# wireframe_sch.net
KiCad netlist of a schematic drawn in Altium Designer
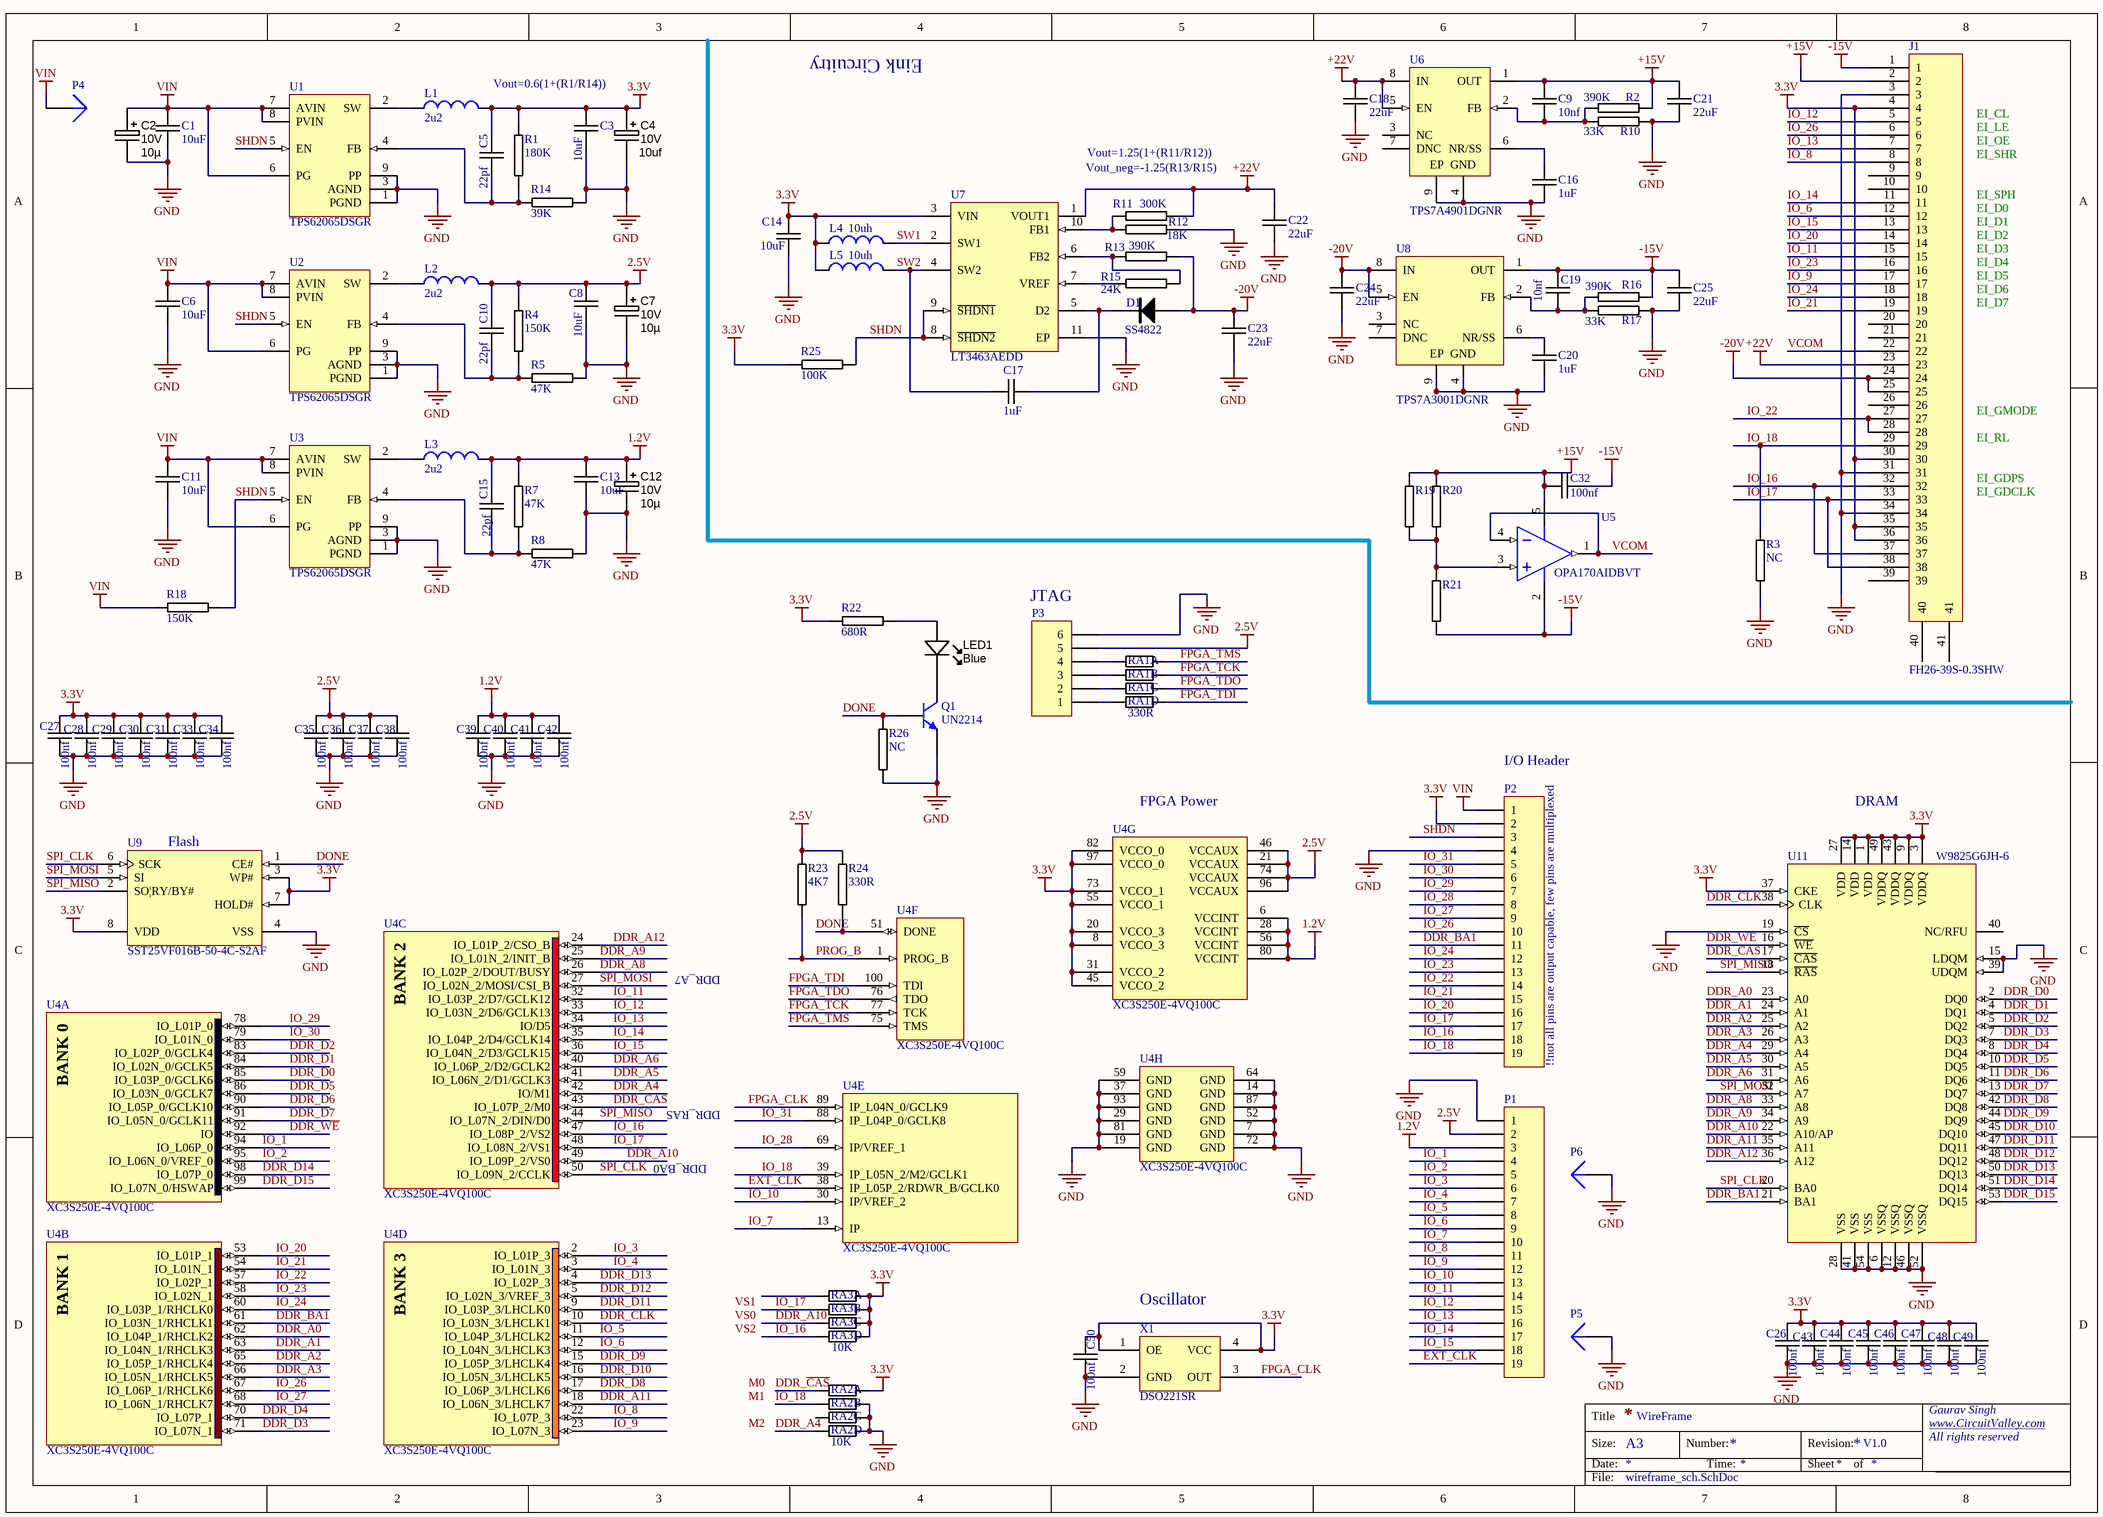
[diagram p0: wireframe_sch.SchDoc]

(export (version "E")
  (design (tool "Eeschema 10.0.6"))
  (components
    (comp (ref "C1")
      (value "10uF")
      (footprint "0603C-GENERIC")
      (description "CAPACITOR 0603 CERAMIC")
      (fields
        (field (name "MANUFACTURER") "Murata Electronics North America")
        (field (name "MANUFACTURER PART NUMBER") "GRM188R60J106ME47D")
      )
      (libsource (lib "Generic") (part "0603C-10UF-6V3-X5R-MUR"))
    )
    (comp (ref "C2")
      (value "10µ")
      (footprint "CAPMP3528X210N")
      (description "Capacitor SMD Tantalum 47uF 20% 6.3V 1210")
      (fields (field (name "TOLERANCE") "±20%") (field (name "RATINGS") "10V"))
      (libsource (lib "PBL - Capacitors") (part "CAPT_47u_1210_6V3"))
    )
    (comp (ref "C3")
      (value "10uF")
      (footprint "0603C-GENERIC")
      (description "CAPACITOR 0603 CERAMIC")
      (fields
        (field (name "MANUFACTURER") "Murata Electronics North America")
        (field (name "MANUFACTURER PART NUMBER") "GRM188R60J106ME47D")
      )
      (libsource (lib "Generic") (part "0603C-10UF-6V3-X5R-MUR"))
    )
    (comp (ref "C4")
      (value "10uf")
      (footprint "CAPMP3528X210N")
      (description "Capacitor SMD Tantalum 47uF 20% 6.3V 1210")
      (fields (field (name "TOLERANCE") "±20%") (field (name "RATINGS") "10V"))
      (libsource (lib "PBL - Capacitors") (part "CAPT_47u_1210_6V3"))
    )
    (comp (ref "C5")
      (value "22pf")
      (footprint "0603C-GENERIC")
      (description "CAPACITOR 0603 CERAMIC")
      (fields
        (field (name "MANUFACTURER") "Murata Electronics North America")
        (field (name "MANUFACTURER PART NUMBER") "GRM188R60J106ME47D")
      )
      (libsource (lib "Generic") (part "0603C-10UF-6V3-X5R-MUR"))
    )
    (comp (ref "C6")
      (value "10uF")
      (footprint "0603C-GENERIC")
      (description "CAPACITOR 0603 CERAMIC")
      (fields
        (field (name "MANUFACTURER") "Murata Electronics North America")
        (field (name "MANUFACTURER PART NUMBER") "GRM188R60J106ME47D")
      )
      (libsource (lib "Generic") (part "0603C-10UF-6V3-X5R-MUR"))
    )
    (comp (ref "C7")
      (value "10µ")
      (footprint "CAPMP3528X210N")
      (description "Capacitor SMD Tantalum 47uF 20% 6.3V 1210")
      (fields (field (name "TOLERANCE") "±20%") (field (name "RATINGS") "10V"))
      (libsource (lib "PBL - Capacitors") (part "CAPT_47u_1210_6V3"))
    )
    (comp (ref "C8")
      (value "10uF")
      (footprint "0603C-GENERIC")
      (description "CAPACITOR 0603 CERAMIC")
      (fields
        (field (name "MANUFACTURER") "Murata Electronics North America")
        (field (name "MANUFACTURER PART NUMBER") "GRM188R60J106ME47D")
      )
      (libsource (lib "Generic") (part "0603C-10UF-6V3-X5R-MUR"))
    )
    (comp (ref "C9")
      (value "10nf")
      (footprint "0603C-GENERIC")
      (description "CAPACITOR 0603 CERAMIC")
      (fields
        (field (name "MANUFACTURER") "Murata Electronics North America")
        (field (name "MANUFACTURER PART NUMBER") "GRM188R60J106ME47D")
      )
      (libsource (lib "Generic") (part "0603C-10UF-6V3-X5R-MUR"))
    )
    (comp (ref "C10")
      (value "22pf")
      (footprint "0603C-GENERIC")
      (description "CAPACITOR 0603 CERAMIC")
      (fields
        (field (name "MANUFACTURER") "Murata Electronics North America")
        (field (name "MANUFACTURER PART NUMBER") "GRM188R60J106ME47D")
      )
      (libsource (lib "Generic") (part "0603C-10UF-6V3-X5R-MUR"))
    )
    (comp (ref "C11")
      (value "10uF")
      (footprint "0603C-GENERIC")
      (description "CAPACITOR 0603 CERAMIC")
      (fields
        (field (name "MANUFACTURER") "Murata Electronics North America")
        (field (name "MANUFACTURER PART NUMBER") "GRM188R60J106ME47D")
      )
      (libsource (lib "Generic") (part "0603C-10UF-6V3-X5R-MUR"))
    )
    (comp (ref "C12")
      (value "10µ")
      (footprint "CAPMP3528X210N")
      (description "Capacitor SMD Tantalum 47uF 20% 6.3V 1210")
      (fields (field (name "TOLERANCE") "±20%") (field (name "RATINGS") "10V"))
      (libsource (lib "PBL - Capacitors") (part "CAPT_47u_1210_6V3"))
    )
    (comp (ref "C13")
      (value "10uF")
      (footprint "0603C-GENERIC")
      (description "CAPACITOR 0603 CERAMIC")
      (fields
        (field (name "MANUFACTURER") "Murata Electronics North America")
        (field (name "MANUFACTURER PART NUMBER") "GRM188R60J106ME47D")
      )
      (libsource (lib "Generic") (part "0603C-10UF-6V3-X5R-MUR"))
    )
    (comp (ref "C14")
      (value "10uF")
      (footprint "0603C-GENERIC")
      (description "CAPACITOR 0603 CERAMIC")
      (fields
        (field (name "MANUFACTURER") "Murata Electronics North America")
        (field (name "MANUFACTURER PART NUMBER") "GRM188R60J106ME47D")
      )
      (libsource (lib "Generic") (part "0603C-10UF-6V3-X5R-MUR"))
    )
    (comp (ref "C15")
      (value "22pf")
      (footprint "0603C-GENERIC")
      (description "CAPACITOR 0603 CERAMIC")
      (fields
        (field (name "MANUFACTURER") "Murata Electronics North America")
        (field (name "MANUFACTURER PART NUMBER") "GRM188R60J106ME47D")
      )
      (libsource (lib "Generic") (part "0603C-10UF-6V3-X5R-MUR"))
    )
    (comp (ref "C16")
      (value "1uF")
      (footprint "0603C-GENERIC")
      (description "CAPACITOR 0603 CERAMIC")
      (fields
        (field (name "MANUFACTURER") "Murata Electronics North America")
        (field (name "MANUFACTURER PART NUMBER") "GRM188R60J106ME47D")
      )
      (libsource (lib "Generic") (part "0603C-10UF-6V3-X5R-MUR"))
    )
    (comp (ref "C17")
      (value "1uF")
      (footprint "0603C-GENERIC")
      (description "CAPACITOR 0603 CERAMIC")
      (fields
        (field (name "MANUFACTURER") "Murata Electronics North America")
        (field (name "MANUFACTURER PART NUMBER") "GRM188R60J106ME47D")
      )
      (libsource (lib "Generic") (part "0603C-10UF-6V3-X5R-MUR"))
    )
    (comp (ref "C18")
      (value "22uF")
      (footprint "0603C-GENERIC")
      (description "CAPACITOR 0603 CERAMIC")
      (fields
        (field (name "MANUFACTURER") "Murata Electronics North America")
        (field (name "MANUFACTURER PART NUMBER") "GRM188R60J106ME47D")
      )
      (libsource (lib "Generic") (part "0603C-10UF-6V3-X5R-MUR"))
    )
    (comp (ref "C19")
      (value "10nf")
      (footprint "0603C-GENERIC")
      (description "CAPACITOR 0603 CERAMIC")
      (fields
        (field (name "MANUFACTURER") "Murata Electronics North America")
        (field (name "MANUFACTURER PART NUMBER") "GRM188R60J106ME47D")
      )
      (libsource (lib "Generic") (part "0603C-10UF-6V3-X5R-MUR"))
    )
    (comp (ref "C20")
      (value "1uF")
      (footprint "0603C-GENERIC")
      (description "CAPACITOR 0603 CERAMIC")
      (fields
        (field (name "MANUFACTURER") "Murata Electronics North America")
        (field (name "MANUFACTURER PART NUMBER") "GRM188R60J106ME47D")
      )
      (libsource (lib "Generic") (part "0603C-10UF-6V3-X5R-MUR"))
    )
    (comp (ref "C21")
      (value "22uF")
      (footprint "0603C-GENERIC")
      (description "CAPACITOR 0603 CERAMIC")
      (fields
        (field (name "MANUFACTURER") "Murata Electronics North America")
        (field (name "MANUFACTURER PART NUMBER") "GRM188R60J106ME47D")
      )
      (libsource (lib "Generic") (part "0603C-10UF-6V3-X5R-MUR"))
    )
    (comp (ref "C22")
      (value "22uF")
      (footprint "0603C-GENERIC")
      (description "CAPACITOR 0603 CERAMIC")
      (fields
        (field (name "MANUFACTURER") "Murata Electronics North America")
        (field (name "MANUFACTURER PART NUMBER") "GRM188R60J106ME47D")
      )
      (libsource (lib "Generic") (part "0603C-10UF-6V3-X5R-MUR"))
    )
    (comp (ref "C23")
      (value "22uF")
      (footprint "0603C-GENERIC")
      (description "CAPACITOR 0603 CERAMIC")
      (fields
        (field (name "MANUFACTURER") "Murata Electronics North America")
        (field (name "MANUFACTURER PART NUMBER") "GRM188R60J106ME47D")
      )
      (libsource (lib "Generic") (part "0603C-10UF-6V3-X5R-MUR"))
    )
    (comp (ref "C24")
      (value "22uF")
      (footprint "0603C-GENERIC")
      (description "CAPACITOR 0603 CERAMIC")
      (fields
        (field (name "MANUFACTURER") "Murata Electronics North America")
        (field (name "MANUFACTURER PART NUMBER") "GRM188R60J106ME47D")
      )
      (libsource (lib "Generic") (part "0603C-10UF-6V3-X5R-MUR"))
    )
    (comp (ref "C25")
      (value "22uF")
      (footprint "0603C-GENERIC")
      (description "CAPACITOR 0603 CERAMIC")
      (fields
        (field (name "MANUFACTURER") "Murata Electronics North America")
        (field (name "MANUFACTURER PART NUMBER") "GRM188R60J106ME47D")
      )
      (libsource (lib "Generic") (part "0603C-10UF-6V3-X5R-MUR"))
    )
    (comp (ref "C26")
      (value "100nf")
      (footprint "0603C-GENERIC")
      (description "CAPACITOR 0603 CERAMIC")
      (fields
        (field (name "MANUFACTURER") "Murata Electronics North America")
        (field (name "MANUFACTURER PART NUMBER") "GRM188R60J106ME47D")
      )
      (libsource (lib "Generic") (part "0603C-10UF-6V3-X5R-MUR"))
    )
    (comp (ref "C27")
      (value "100nf")
      (footprint "0603C-GENERIC")
      (description "CAPACITOR 0603 CERAMIC")
      (fields
        (field (name "MANUFACTURER") "Murata Electronics North America")
        (field (name "MANUFACTURER PART NUMBER") "GRM188R60J106ME47D")
      )
      (libsource (lib "Generic") (part "0603C-10UF-6V3-X5R-MUR"))
    )
    (comp (ref "C28")
      (value "100nf")
      (footprint "0603C-GENERIC")
      (description "CAPACITOR 0603 CERAMIC")
      (fields
        (field (name "MANUFACTURER") "Murata Electronics North America")
        (field (name "MANUFACTURER PART NUMBER") "GRM188R60J106ME47D")
      )
      (libsource (lib "Generic") (part "0603C-10UF-6V3-X5R-MUR"))
    )
    (comp (ref "C29")
      (value "100nf")
      (footprint "0603C-GENERIC")
      (description "CAPACITOR 0603 CERAMIC")
      (fields
        (field (name "MANUFACTURER") "Murata Electronics North America")
        (field (name "MANUFACTURER PART NUMBER") "GRM188R60J106ME47D")
      )
      (libsource (lib "Generic") (part "0603C-10UF-6V3-X5R-MUR"))
    )
    (comp (ref "C30")
      (value "100nf")
      (footprint "0603C-GENERIC")
      (description "CAPACITOR 0603 CERAMIC")
      (fields
        (field (name "MANUFACTURER") "Murata Electronics North America")
        (field (name "MANUFACTURER PART NUMBER") "GRM188R60J106ME47D")
      )
      (libsource (lib "Generic") (part "0603C-10UF-6V3-X5R-MUR"))
    )
    (comp (ref "C31")
      (value "100nf")
      (footprint "0603C-GENERIC")
      (description "CAPACITOR 0603 CERAMIC")
      (fields
        (field (name "MANUFACTURER") "Murata Electronics North America")
        (field (name "MANUFACTURER PART NUMBER") "GRM188R60J106ME47D")
      )
      (libsource (lib "Generic") (part "0603C-10UF-6V3-X5R-MUR"))
    )
    (comp (ref "C32")
      (value "100nf")
      (footprint "0603C-GENERIC")
      (description "CAPACITOR 0603 CERAMIC")
      (fields
        (field (name "MANUFACTURER") "Murata Electronics North America")
        (field (name "MANUFACTURER PART NUMBER") "GRM188R60J106ME47D")
      )
      (libsource (lib "Generic") (part "0603C-10UF-6V3-X5R-MUR"))
    )
    (comp (ref "C33")
      (value "100nf")
      (footprint "0603C-GENERIC")
      (description "CAPACITOR 0603 CERAMIC")
      (fields
        (field (name "MANUFACTURER") "Murata Electronics North America")
        (field (name "MANUFACTURER PART NUMBER") "GRM188R60J106ME47D")
      )
      (libsource (lib "Generic") (part "0603C-10UF-6V3-X5R-MUR"))
    )
    (comp (ref "C34")
      (value "100nf")
      (footprint "0603C-GENERIC")
      (description "CAPACITOR 0603 CERAMIC")
      (fields
        (field (name "MANUFACTURER") "Murata Electronics North America")
        (field (name "MANUFACTURER PART NUMBER") "GRM188R60J106ME47D")
      )
      (libsource (lib "Generic") (part "0603C-10UF-6V3-X5R-MUR"))
    )
    (comp (ref "C35")
      (value "100nf")
      (footprint "0603C-GENERIC")
      (description "CAPACITOR 0603 CERAMIC")
      (fields
        (field (name "MANUFACTURER") "Murata Electronics North America")
        (field (name "MANUFACTURER PART NUMBER") "GRM188R60J106ME47D")
      )
      (libsource (lib "Generic") (part "0603C-10UF-6V3-X5R-MUR"))
    )
    (comp (ref "C36")
      (value "100nf")
      (footprint "0603C-GENERIC")
      (description "CAPACITOR 0603 CERAMIC")
      (fields
        (field (name "MANUFACTURER") "Murata Electronics North America")
        (field (name "MANUFACTURER PART NUMBER") "GRM188R60J106ME47D")
      )
      (libsource (lib "Generic") (part "0603C-10UF-6V3-X5R-MUR"))
    )
    (comp (ref "C37")
      (value "100nf")
      (footprint "0603C-GENERIC")
      (description "CAPACITOR 0603 CERAMIC")
      (fields
        (field (name "MANUFACTURER") "Murata Electronics North America")
        (field (name "MANUFACTURER PART NUMBER") "GRM188R60J106ME47D")
      )
      (libsource (lib "Generic") (part "0603C-10UF-6V3-X5R-MUR"))
    )
    (comp (ref "C38")
      (value "100nf")
      (footprint "0603C-GENERIC")
      (description "CAPACITOR 0603 CERAMIC")
      (fields
        (field (name "MANUFACTURER") "Murata Electronics North America")
        (field (name "MANUFACTURER PART NUMBER") "GRM188R60J106ME47D")
      )
      (libsource (lib "Generic") (part "0603C-10UF-6V3-X5R-MUR"))
    )
    (comp (ref "C39")
      (value "100nf")
      (footprint "0603C-GENERIC")
      (description "CAPACITOR 0603 CERAMIC")
      (fields
        (field (name "MANUFACTURER") "Murata Electronics North America")
        (field (name "MANUFACTURER PART NUMBER") "GRM188R60J106ME47D")
      )
      (libsource (lib "Generic") (part "0603C-10UF-6V3-X5R-MUR"))
    )
    (comp (ref "C40")
      (value "100nf")
      (footprint "0603C-GENERIC")
      (description "CAPACITOR 0603 CERAMIC")
      (fields
        (field (name "MANUFACTURER") "Murata Electronics North America")
        (field (name "MANUFACTURER PART NUMBER") "GRM188R60J106ME47D")
      )
      (libsource (lib "Generic") (part "0603C-10UF-6V3-X5R-MUR"))
    )
    (comp (ref "C41")
      (value "100nf")
      (footprint "0603C-GENERIC")
      (description "CAPACITOR 0603 CERAMIC")
      (fields
        (field (name "MANUFACTURER") "Murata Electronics North America")
        (field (name "MANUFACTURER PART NUMBER") "GRM188R60J106ME47D")
      )
      (libsource (lib "Generic") (part "0603C-10UF-6V3-X5R-MUR"))
    )
    (comp (ref "C42")
      (value "100nf")
      (footprint "0603C-GENERIC")
      (description "CAPACITOR 0603 CERAMIC")
      (fields
        (field (name "MANUFACTURER") "Murata Electronics North America")
        (field (name "MANUFACTURER PART NUMBER") "GRM188R60J106ME47D")
      )
      (libsource (lib "Generic") (part "0603C-10UF-6V3-X5R-MUR"))
    )
    (comp (ref "C43")
      (value "100nf")
      (footprint "0603C-GENERIC")
      (description "CAPACITOR 0603 CERAMIC")
      (fields
        (field (name "MANUFACTURER") "Murata Electronics North America")
        (field (name "MANUFACTURER PART NUMBER") "GRM188R60J106ME47D")
      )
      (libsource (lib "Generic") (part "0603C-10UF-6V3-X5R-MUR"))
    )
    (comp (ref "C44")
      (value "100nf")
      (footprint "0603C-GENERIC")
      (description "CAPACITOR 0603 CERAMIC")
      (fields
        (field (name "MANUFACTURER") "Murata Electronics North America")
        (field (name "MANUFACTURER PART NUMBER") "GRM188R60J106ME47D")
      )
      (libsource (lib "Generic") (part "0603C-10UF-6V3-X5R-MUR"))
    )
    (comp (ref "C45")
      (value "100nf")
      (footprint "0603C-GENERIC")
      (description "CAPACITOR 0603 CERAMIC")
      (fields
        (field (name "MANUFACTURER") "Murata Electronics North America")
        (field (name "MANUFACTURER PART NUMBER") "GRM188R60J106ME47D")
      )
      (libsource (lib "Generic") (part "0603C-10UF-6V3-X5R-MUR"))
    )
    (comp (ref "C46")
      (value "100nf")
      (footprint "0603C-GENERIC")
      (description "CAPACITOR 0603 CERAMIC")
      (fields
        (field (name "MANUFACTURER") "Murata Electronics North America")
        (field (name "MANUFACTURER PART NUMBER") "GRM188R60J106ME47D")
      )
      (libsource (lib "Generic") (part "0603C-10UF-6V3-X5R-MUR"))
    )
    (comp (ref "C47")
      (value "100nf")
      (footprint "0603C-GENERIC")
      (description "CAPACITOR 0603 CERAMIC")
      (fields
        (field (name "MANUFACTURER") "Murata Electronics North America")
        (field (name "MANUFACTURER PART NUMBER") "GRM188R60J106ME47D")
      )
      (libsource (lib "Generic") (part "0603C-10UF-6V3-X5R-MUR"))
    )
    (comp (ref "C48")
      (value "100nf")
      (footprint "0603C-GENERIC")
      (description "CAPACITOR 0603 CERAMIC")
      (fields
        (field (name "MANUFACTURER") "Murata Electronics North America")
        (field (name "MANUFACTURER PART NUMBER") "GRM188R60J106ME47D")
      )
      (libsource (lib "Generic") (part "0603C-10UF-6V3-X5R-MUR"))
    )
    (comp (ref "C49")
      (value "100nf")
      (footprint "0603C-GENERIC")
      (description "CAPACITOR 0603 CERAMIC")
      (fields
        (field (name "MANUFACTURER") "Murata Electronics North America")
        (field (name "MANUFACTURER PART NUMBER") "GRM188R60J106ME47D")
      )
      (libsource (lib "Generic") (part "0603C-10UF-6V3-X5R-MUR"))
    )
    (comp (ref "C50")
      (value "100nf")
      (footprint "0603C-GENERIC")
      (description "CAPACITOR 0603 CERAMIC")
      (fields
        (field (name "MANUFACTURER") "Murata Electronics North America")
        (field (name "MANUFACTURER PART NUMBER") "GRM188R60J106ME47D")
      )
      (libsource (lib "Generic") (part "0603C-10UF-6V3-X5R-MUR"))
    )
    (comp (ref "D1")
      (value "SS4822")
      (footprint "DIODE-SMA")
      (description "DIODE")
      (libsource (lib "Generic") (part "MBRS140"))
    )
    (comp (ref "J1")
      (value "FH26-39S-0.3SHW")
      (footprint "FH26-39S-0.3SHW")
      (libsource (lib "Hiros") (part "FH26-39S-0.3SHW"))
    )
    (comp (ref "L1")
      (value "2u2")
      (footprint "TAIYO_NRS4018T2R2MDGJ")
      (fields (field (name "PARTNUMBER") "NRS4018T2R2MDGJ"))
      (libsource (lib "Inductor") (part "inductor_smd"))
    )
    (comp (ref "L2")
      (value "2u2")
      (footprint "TAIYO_NRS4018T2R2MDGJ")
      (fields (field (name "PARTNUMBER") "NRS4018T2R2MDGJ"))
      (libsource (lib "Inductor") (part "inductor_smd"))
    )
    (comp (ref "L3")
      (value "2u2")
      (footprint "TAIYO_NRS4018T2R2MDGJ")
      (fields (field (name "PARTNUMBER") "NRS4018T2R2MDGJ"))
      (libsource (lib "Inductor") (part "inductor_smd"))
    )
    (comp (ref "L4")
      (value "10uh")
      (footprint "IFSC-1515AH-01")
      (fields (field (name "PARTNUMBER") "IFSC1515AHER100M01"))
      (libsource (lib "Inductor") (part "inductor_smd"))
    )
    (comp (ref "L5")
      (value "10uh")
      (footprint "IFSC-1515AH-01")
      (fields (field (name "PARTNUMBER") "IFSC1515AHER100M01"))
      (libsource (lib "Inductor") (part "inductor_smd"))
    )
    (comp (ref "LED1")
      (value "Blue")
      (footprint "LED-0805-K")
      (description "LED 0805 SMD Blue 100mcd 470nm")
      (fields (field (name "COLOR") "Blue"))
      (libsource (lib "PBL - Light Sources") (part "LED_SMD_Blue_0805_100mcd"))
    )
    (comp (ref "P1")
      (value "Header 19")
      (footprint "HDR1X19")
      (description "Header, 19-Pin")
      (fields (field (name "PUBLISHER") "Altium Limited"))
      (libsource (lib "Miscellaneous Connectors") (part "Header 19"))
    )
    (comp (ref "P2")
      (value "Header 19")
      (footprint "HDR1X19")
      (description "Header, 19-Pin")
      (fields (field (name "PUBLISHER") "Altium Limited"))
      (libsource (lib "Miscellaneous Connectors") (part "Header 19"))
    )
    (comp (ref "P3")
      (value "Header 6")
      (footprint "HDR1X6")
      (description "Header, 6-Pin")
      (fields (field (name "PUBLISHER") "Altium Limited"))
      (libsource (lib "Miscellaneous Connectors") (part "Header 6"))
    )
    (comp (ref "P4")
      (value "Plug")
      (footprint "PIN1")
      (fields (field (name "PUBLISHER") "Altium Limited"))
      (libsource (lib "Miscellaneous Connectors") (part "Plug"))
    )
    (comp (ref "P5")
      (value "Plug")
      (footprint "PIN1")
      (fields (field (name "PUBLISHER") "Altium Limited"))
      (libsource (lib "Miscellaneous Connectors") (part "Plug"))
    )
    (comp (ref "P6")
      (value "Plug")
      (footprint "PIN1")
      (fields (field (name "PUBLISHER") "Altium Limited"))
      (libsource (lib "Miscellaneous Connectors") (part "Plug"))
    )
    (comp (ref "Q1")
      (value "UN2214")
      (footprint "SOT23_N")
      (description "NPN General-purpose Transistor")
      (fields (field (name "PUBLISHER") "Altium Limited"))
      (libsource (lib "Philips Discrete BJT - Low Power") (part "BC847"))
    )
    (comp (ref "R1")
      (value "180K")
      (footprint "0603R-2K2")
      (description "GENERIC RESISTOR 0603")
      (fields
        (field (name "MANUFACTURER PART NUMBER") "RMC 1/16 2.2K 1% R")
        (field (name "MANUFACTURER") "Stackpole Electronics Inc")
      )
      (libsource (lib "Generic") (part "0603R-2K2"))
    )
    (comp (ref "R2")
      (value "390K")
      (footprint "0603R-2K2")
      (description "GENERIC RESISTOR 0603")
      (fields
        (field (name "MANUFACTURER PART NUMBER") "RMC 1/16 2.2K 1% R")
        (field (name "MANUFACTURER") "Stackpole Electronics Inc")
      )
      (libsource (lib "Generic") (part "0603R-2K2"))
    )
    (comp (ref "R3")
      (value "NC")
      (footprint "0402R-GENERIC")
      (description "RESISTOR 0402 GENERIC")
      (libsource (lib "Generic") (part "0402R-100R"))
    )
    (comp (ref "R4")
      (value "150K")
      (footprint "0603R-2K2")
      (description "GENERIC RESISTOR 0603")
      (fields
        (field (name "MANUFACTURER PART NUMBER") "RMC 1/16 2.2K 1% R")
        (field (name "MANUFACTURER") "Stackpole Electronics Inc")
      )
      (libsource (lib "Generic") (part "0603R-2K2"))
    )
    (comp (ref "R5")
      (value "47K")
      (footprint "0603R-2K2")
      (description "GENERIC RESISTOR 0603")
      (fields
        (field (name "MANUFACTURER PART NUMBER") "RMC 1/16 2.2K 1% R")
        (field (name "MANUFACTURER") "Stackpole Electronics Inc")
      )
      (libsource (lib "Generic") (part "0603R-2K2"))
    )
    (comp (ref "R7")
      (value "47K")
      (footprint "0603R-2K2")
      (description "GENERIC RESISTOR 0603")
      (fields
        (field (name "MANUFACTURER PART NUMBER") "RMC 1/16 2.2K 1% R")
        (field (name "MANUFACTURER") "Stackpole Electronics Inc")
      )
      (libsource (lib "Generic") (part "0603R-2K2"))
    )
    (comp (ref "R8")
      (value "47K")
      (footprint "0603R-2K2")
      (description "GENERIC RESISTOR 0603")
      (fields
        (field (name "MANUFACTURER PART NUMBER") "RMC 1/16 2.2K 1% R")
        (field (name "MANUFACTURER") "Stackpole Electronics Inc")
      )
      (libsource (lib "Generic") (part "0603R-2K2"))
    )
    (comp (ref "R10")
      (value "33K")
      (footprint "0603R-2K2")
      (description "GENERIC RESISTOR 0603")
      (fields
        (field (name "MANUFACTURER PART NUMBER") "RMC 1/16 2.2K 1% R")
        (field (name "MANUFACTURER") "Stackpole Electronics Inc")
      )
      (libsource (lib "Generic") (part "0603R-2K2"))
    )
    (comp (ref "R11")
      (value "300K")
      (footprint "0603R-2K2")
      (description "GENERIC RESISTOR 0603")
      (fields
        (field (name "MANUFACTURER PART NUMBER") "RMC 1/16 2.2K 1% R")
        (field (name "MANUFACTURER") "Stackpole Electronics Inc")
      )
      (libsource (lib "Generic") (part "0603R-2K2"))
    )
    (comp (ref "R12")
      (value "18K")
      (footprint "0603R-2K2")
      (description "GENERIC RESISTOR 0603")
      (fields
        (field (name "MANUFACTURER PART NUMBER") "RMC 1/16 2.2K 1% R")
        (field (name "MANUFACTURER") "Stackpole Electronics Inc")
      )
      (libsource (lib "Generic") (part "0603R-2K2"))
    )
    (comp (ref "R13")
      (value "390K")
      (footprint "0603R-2K2")
      (description "GENERIC RESISTOR 0603")
      (fields
        (field (name "MANUFACTURER PART NUMBER") "RMC 1/16 2.2K 1% R")
        (field (name "MANUFACTURER") "Stackpole Electronics Inc")
      )
      (libsource (lib "Generic") (part "0603R-2K2"))
    )
    (comp (ref "R14")
      (value "39K")
      (footprint "0603R-2K2")
      (description "GENERIC RESISTOR 0603")
      (fields
        (field (name "MANUFACTURER PART NUMBER") "RMC 1/16 2.2K 1% R")
        (field (name "MANUFACTURER") "Stackpole Electronics Inc")
      )
      (libsource (lib "Generic") (part "0603R-2K2"))
    )
    (comp (ref "R15")
      (value "24K")
      (footprint "0603R-2K2")
      (description "GENERIC RESISTOR 0603")
      (fields
        (field (name "MANUFACTURER PART NUMBER") "RMC 1/16 2.2K 1% R")
        (field (name "MANUFACTURER") "Stackpole Electronics Inc")
      )
      (libsource (lib "Generic") (part "0603R-2K2"))
    )
    (comp (ref "R16")
      (value "390K")
      (footprint "0603R-2K2")
      (description "GENERIC RESISTOR 0603")
      (fields
        (field (name "MANUFACTURER PART NUMBER") "RMC 1/16 2.2K 1% R")
        (field (name "MANUFACTURER") "Stackpole Electronics Inc")
      )
      (libsource (lib "Generic") (part "0603R-2K2"))
    )
    (comp (ref "R17")
      (value "33K")
      (footprint "0603R-2K2")
      (description "GENERIC RESISTOR 0603")
      (fields
        (field (name "MANUFACTURER PART NUMBER") "RMC 1/16 2.2K 1% R")
        (field (name "MANUFACTURER") "Stackpole Electronics Inc")
      )
      (libsource (lib "Generic") (part "0603R-2K2"))
    )
    (comp (ref "R18")
      (value "150K")
      (footprint "0603R-2K2")
      (description "GENERIC RESISTOR 0603")
      (fields
        (field (name "MANUFACTURER PART NUMBER") "RMC 1/16 2.2K 1% R")
        (field (name "MANUFACTURER") "Stackpole Electronics Inc")
      )
      (libsource (lib "Generic") (part "0603R-2K2"))
    )
    (comp (ref "R19")
      (value "unknown")
      (footprint "0603R-2K2")
      (description "GENERIC RESISTOR 0603")
      (fields
        (field (name "MANUFACTURER PART NUMBER") "RMC 1/16 2.2K 1% R")
        (field (name "MANUFACTURER") "Stackpole Electronics Inc")
      )
      (libsource (lib "Generic") (part "0603R-2K2"))
    )
    (comp (ref "R20")
      (value "unknown")
      (footprint "0603R-2K2")
      (description "GENERIC RESISTOR 0603")
      (fields
        (field (name "MANUFACTURER PART NUMBER") "RMC 1/16 2.2K 1% R")
        (field (name "MANUFACTURER") "Stackpole Electronics Inc")
      )
      (libsource (lib "Generic") (part "0603R-2K2"))
    )
    (comp (ref "R21")
      (value "unknown")
      (footprint "0603R-2K2")
      (description "GENERIC RESISTOR 0603")
      (fields
        (field (name "MANUFACTURER PART NUMBER") "RMC 1/16 2.2K 1% R")
        (field (name "MANUFACTURER") "Stackpole Electronics Inc")
      )
      (libsource (lib "Generic") (part "0603R-2K2"))
    )
    (comp (ref "R22")
      (value "680R")
      (footprint "0603R-2K2")
      (description "GENERIC RESISTOR 0603")
      (fields
        (field (name "MANUFACTURER PART NUMBER") "RMC 1/16 2.2K 1% R")
        (field (name "MANUFACTURER") "Stackpole Electronics Inc")
      )
      (libsource (lib "Generic") (part "0603R-2K2"))
    )
    (comp (ref "R23")
      (value "4K7")
      (footprint "0603R-2K2")
      (description "GENERIC RESISTOR 0603")
      (fields
        (field (name "MANUFACTURER PART NUMBER") "RMC 1/16 2.2K 1% R")
        (field (name "MANUFACTURER") "Stackpole Electronics Inc")
      )
      (libsource (lib "Generic") (part "0603R-2K2"))
    )
    (comp (ref "R24")
      (value "330R")
      (footprint "0603R-2K2")
      (description "GENERIC RESISTOR 0603")
      (fields
        (field (name "MANUFACTURER PART NUMBER") "RMC 1/16 2.2K 1% R")
        (field (name "MANUFACTURER") "Stackpole Electronics Inc")
      )
      (libsource (lib "Generic") (part "0603R-2K2"))
    )
    (comp (ref "R25")
      (value "100K")
      (footprint "0603R-2K2")
      (description "GENERIC RESISTOR 0603")
      (fields
        (field (name "MANUFACTURER PART NUMBER") "RMC 1/16 2.2K 1% R")
        (field (name "MANUFACTURER") "Stackpole Electronics Inc")
      )
      (libsource (lib "Generic") (part "0603R-2K2"))
    )
    (comp (ref "R26")
      (value "NC")
      (footprint "0402R-GENERIC")
      (description "RESISTOR 0402 GENERIC")
      (libsource (lib "Generic") (part "0402R-100R"))
    )
    (comp (ref "RA1")
      (value "Thick Film")
      (footprint "EXV28V")
      (description "Resistor array 4-pack 5% 0402 SMD")
      (libsource (lib "resistors") (part "RES_ARRAY_0402_5%"))
    )
    (comp (ref "RA2")
      (value "10K")
      (footprint "EXV28V")
      (description "Resistor array 4-pack 5% 0402 SMD")
      (libsource (lib "resistors") (part "RES_ARRAY_0402_5%"))
    )
    (comp (ref "RA3")
      (value "Thick Film")
      (footprint "EXV28V")
      (description "Resistor array 4-pack 5% 0402 SMD")
      (libsource (lib "resistors") (part "RES_ARRAY_0402_5%"))
    )
    (comp (ref "U1")
      (value "TPS62065DSGR")
      (footprint "DSG8-1600X900TP")
      (fields (field (name "MANUFACTURER") "Texas Instruments") (field (name "PARTNUMBER") "TPS62067DSGR"))
      (libsource (lib "TI Power Management Step-Down Regulator") (part "TPS62067DSGR"))
    )
    (comp (ref "U2")
      (value "TPS62065DSGR")
      (footprint "DSG8-1600X900TP")
      (fields (field (name "MANUFACTURER") "Texas Instruments") (field (name "PARTNUMBER") "TPS62067DSGR"))
      (libsource (lib "TI Power Management Step-Down Regulator") (part "TPS62067DSGR"))
    )
    (comp (ref "U3")
      (value "TPS62065DSGR")
      (footprint "DSG8-1600X900TP")
      (fields (field (name "MANUFACTURER") "Texas Instruments") (field (name "PARTNUMBER") "TPS62067DSGR"))
      (libsource (lib "TI Power Management Step-Down Regulator") (part "TPS62067DSGR"))
    )
    (comp (ref "U4")
      (value "XC3S250E-4VQ100C")
      (footprint "VQ100_N")
      (description "Spartan-3E 1.2V FPGA, 66 User I/Os, 100-Pin VQFP, Standard Performance, Commercial Grade")
      (libsource (lib "Xilinx Spartan-3E") (part "XC3S250E-4VQ100C"))
    )
    (comp (ref "U5")
      (value "OPA170AIDBVT")
      (footprint "TI-DBV5_N")
      (fields (field (name "MANUFACTURER") "Texas Instruments"))
      (libsource (lib "TI Amplifiers and Linear Operational Amplifier Precision Amplifier Part One") (part "OPA244NA/250"))
    )
    (comp (ref "U6")
      (value "TPS7A4901DGNR")
      (footprint "TI-DGN8-1760X1425TP_N")
      (fields (field (name "MANUFACTURER") "Texas Instruments"))
      (libsource (lib "TI Power Management Linear Regulator Single Channel LDO (0-350mA)") (part "TPS7A4901DGNR"))
    )
    (comp (ref "U7")
      (value "LT3463AEDD")
      (footprint "LT-DD-10_V")
      (fields (field (name "MANUFACTURER") "Linear Technology"))
      (libsource (lib "Linear Technology Power Management PMIC Multifunction") (part "LT3463AEDD"))
    )
    (comp (ref "U8")
      (value "TPS7A3001DGNR")
      (footprint "TI-DGN8-1760X1425TP_N")
      (fields (field (name "MANUFACTURER") "Texas Instruments"))
      (libsource (lib "TI Power Management Linear Regulator Single Channel LDO (0-350mA)") (part "TPS7A3001DGNR"))
    )
    (comp (ref "U9")
      (value "SST25VF016B-50-4C-S2AF")
      (footprint "MCHP-SOIC-S2A8_N")
      (description "16 Mbit SPI Serial Flash, 2.7 to 3.6 V, 50 MHz, 0 to 70 degC, 8-pin SOIC (S2A8), Tube")
      (fields (field (name "MANUFACTURER") "Microchip"))
      (libsource (lib "Microchip SST Flash") (part "SST25VF016B-50-4C-S2AF"))
    )
    (comp (ref "U11")
      (value "W9825G6JH-6")
      (footprint "54_TSOP2_400AF_N")
      (description "512Mb Synchronous High Data Rate DRAM, 8Mb x 16Bit x 4 Banks, 54-Pin TSOP")
      (fields (field (name "PUBLISHER") "Altium Limited"))
      (libsource (lib "Samsung Memory Dynamic RAM") (part "K4S511632B-TC75"))
    )
    (comp (ref "X1")
      (value "DSO221SR")
      (footprint "Active Oscillator 2520")
      (description "Active Oscillator_2520")
      (libsource (lib "Crystal_and_oscillator") (part "Oscillator_2520"))
    )
  )
  (nets
    (net (code "1") (name "+15V") (class "Default")
      (node (ref "C21") (pin "2") (pintype "passive"))
      (node (ref "C32") (pin "2") (pintype "passive"))
      (node (ref "C9") (pin "1") (pintype "passive"))
      (node (ref "J1") (pin "2") (pinfunction "2_2") (pintype "passive"))
      (node (ref "R19") (pin "2") (pintype "passive"))
      (node (ref "R2") (pin "2") (pintype "passive"))
      (node (ref "R20") (pin "2") (pintype "passive"))
      (node (ref "U5") (pin "5") (pinfunction "V+_5") (pintype "power_in"))
      (node (ref "U6") (pin "1") (pinfunction "OUT_1") (pintype "power_in"))
    )
    (net (code "2") (name "+22V") (class "Default")
      (node (ref "C18") (pin "2") (pintype "passive"))
      (node (ref "C22") (pin "2") (pintype "passive"))
      (node (ref "J1") (pin "23") (pinfunction "23_23") (pintype "passive"))
      (node (ref "R11") (pin "2") (pintype "passive"))
      (node (ref "U6") (pin "5") (pinfunction "EN_5") (pintype "input"))
      (node (ref "U6") (pin "8") (pinfunction "IN_8") (pintype "power_in"))
      (node (ref "U7") (pin "1") (pinfunction "VOUT1_1") (pintype "power_in"))
    )
    (net (code "3") (name "-15V") (class "Default")
      (node (ref "C19") (pin "1") (pintype "passive"))
      (node (ref "C25") (pin "2") (pintype "passive"))
      (node (ref "C32") (pin "1") (pintype "passive"))
      (node (ref "J1") (pin "1") (pinfunction "1_1") (pintype "passive"))
      (node (ref "R16") (pin "2") (pintype "passive"))
      (node (ref "R21") (pin "1") (pintype "passive"))
      (node (ref "U5") (pin "2") (pinfunction "V-_2") (pintype "power_in"))
      (node (ref "U8") (pin "1") (pinfunction "OUT_1") (pintype "power_in"))
    )
    (net (code "4") (name "-20V") (class "Default")
      (node (ref "C23") (pin "2") (pintype "passive"))
      (node (ref "C24") (pin "2") (pintype "passive"))
      (node (ref "D1") (pin "A") (pinfunction "A_A") (pintype "passive"))
      (node (ref "J1") (pin "24") (pinfunction "24_24") (pintype "passive"))
      (node (ref "J1") (pin "25") (pinfunction "25_25") (pintype "passive"))
      (node (ref "R13") (pin "2") (pintype "passive"))
      (node (ref "U8") (pin "5") (pinfunction "EN_5") (pintype "input"))
      (node (ref "U8") (pin "8") (pinfunction "IN_8") (pintype "power_in"))
    )
    (net (code "5") (name "/DDR_A0") (class "Default")
      (node (ref "U11") (pin "23") (pinfunction "A0_23") (pintype "input"))
      (node (ref "U4") (pin "62") (pinfunction "IO_L04P_1/RHCLK2_62") (pintype "bidirectional"))
    )
    (net (code "6") (name "/DDR_A1") (class "Default")
      (node (ref "U11") (pin "24") (pinfunction "A1_24") (pintype "input"))
      (node (ref "U4") (pin "63") (pinfunction "IO_L04N_1/RHCLK3_63") (pintype "bidirectional"))
    )
    (net (code "7") (name "/DDR_A2") (class "Default")
      (node (ref "U11") (pin "25") (pinfunction "A2_25") (pintype "input"))
      (node (ref "U4") (pin "65") (pinfunction "IO_L05P_1/RHCLK4_65") (pintype "bidirectional"))
    )
    (net (code "8") (name "/DDR_A3") (class "Default")
      (node (ref "U11") (pin "26") (pinfunction "A3_26") (pintype "input"))
      (node (ref "U4") (pin "66") (pinfunction "IO_L05N_1/RHCLK5_66") (pintype "bidirectional"))
    )
    (net (code "9") (name "/DDR_A4") (class "Default")
      (node (ref "RA2") (pin "5") (pinfunction "5_5") (pintype "passive"))
      (node (ref "U11") (pin "29") (pinfunction "A4_29") (pintype "input"))
      (node (ref "U4") (pin "42") (pinfunction "IO/M1_42") (pintype "bidirectional"))
    )
    (net (code "10") (name "/DDR_A5") (class "Default")
      (node (ref "U11") (pin "30") (pinfunction "A5_30") (pintype "input"))
      (node (ref "U4") (pin "41") (pinfunction "IO_L06N_2/D1/GCLK3_41") (pintype "bidirectional"))
    )
    (net (code "11") (name "/DDR_A6") (class "Default")
      (node (ref "U11") (pin "31") (pinfunction "A6_31") (pintype "input"))
      (node (ref "U4") (pin "40") (pinfunction "IO_L06P_2/D2/GCLK2_40") (pintype "bidirectional"))
    )
    (net (code "12") (name "/DDR_A8") (class "Default")
      (node (ref "U11") (pin "33") (pinfunction "A8_33") (pintype "input"))
      (node (ref "U4") (pin "26") (pinfunction "IO_L02P_2/DOUT/BUSY_26") (pintype "bidirectional"))
    )
    (net (code "13") (name "/DDR_A9") (class "Default")
      (node (ref "U11") (pin "34") (pinfunction "A9_34") (pintype "input"))
      (node (ref "U4") (pin "25") (pinfunction "IO_L01N_2/INIT_B_25") (pintype "bidirectional"))
    )
    (net (code "14") (name "/DDR_A10") (class "Default")
      (node (ref "RA3") (pin "6") (pinfunction "6_6") (pintype "passive"))
      (node (ref "U11") (pin "22") (pinfunction "A10/AP_22") (pintype "input"))
      (node (ref "U4") (pin "49") (pinfunction "IO_L09P_2/VS0_49") (pintype "bidirectional"))
    )
    (net (code "15") (name "/DDR_A11") (class "Default")
      (node (ref "U11") (pin "35") (pinfunction "A11_35") (pintype "input"))
      (node (ref "U4") (pin "18") (pinfunction "IO_L06N_3/LHCLK7_18") (pintype "bidirectional"))
    )
    (net (code "16") (name "/DDR_A12") (class "Default")
      (node (ref "U11") (pin "36") (pinfunction "A12_36") (pintype "input"))
      (node (ref "U4") (pin "24") (pinfunction "IO_L01P_2/CSO_B_24") (pintype "bidirectional"))
    )
    (net (code "17") (name "/DDR_BA1") (class "Default")
      (node (ref "P2") (pin "11") (pinfunction "11_11") (pintype "passive"))
      (node (ref "U11") (pin "21") (pinfunction "BA1_21") (pintype "input"))
      (node (ref "U4") (pin "61") (pinfunction "IO_L03N_1/RHCLK1_61") (pintype "bidirectional"))
    )
    (net (code "18") (name "/DDR_CLK") (class "Default")
      (node (ref "U11") (pin "38") (pinfunction "CLK_38") (pintype "input"))
      (node (ref "U4") (pin "10") (pinfunction "IO_L03N_3/LHCLK1_10") (pintype "bidirectional"))
    )
    (net (code "19") (name "/DDR_D0") (class "Default")
      (node (ref "U11") (pin "2") (pinfunction "DQ0_2") (pintype "bidirectional"))
      (node (ref "U4") (pin "85") (pinfunction "IO_L03P_0/GCLK6_85") (pintype "bidirectional"))
    )
    (net (code "20") (name "/DDR_D1") (class "Default")
      (node (ref "U11") (pin "4") (pinfunction "DQ1_4") (pintype "bidirectional"))
      (node (ref "U4") (pin "84") (pinfunction "IO_L02N_0/GCLK5_84") (pintype "bidirectional"))
    )
    (net (code "21") (name "/DDR_D2") (class "Default")
      (node (ref "U11") (pin "5") (pinfunction "DQ2_5") (pintype "bidirectional"))
      (node (ref "U4") (pin "83") (pinfunction "IO_L02P_0/GCLK4_83") (pintype "bidirectional"))
    )
    (net (code "22") (name "/DDR_D3") (class "Default")
      (node (ref "U11") (pin "7") (pinfunction "DQ3_7") (pintype "bidirectional"))
      (node (ref "U4") (pin "71") (pinfunction "IO_L07N_1_71") (pintype "bidirectional"))
    )
    (net (code "23") (name "/DDR_D4") (class "Default")
      (node (ref "U11") (pin "8") (pinfunction "DQ4_8") (pintype "bidirectional"))
      (node (ref "U4") (pin "70") (pinfunction "IO_L07P_1_70") (pintype "bidirectional"))
    )
    (net (code "24") (name "/DDR_D5") (class "Default")
      (node (ref "U11") (pin "10") (pinfunction "DQ5_10") (pintype "bidirectional"))
      (node (ref "U4") (pin "86") (pinfunction "IO_L03N_0/GCLK7_86") (pintype "bidirectional"))
    )
    (net (code "25") (name "/DDR_D6") (class "Default")
      (node (ref "U11") (pin "11") (pinfunction "DQ6_11") (pintype "bidirectional"))
      (node (ref "U4") (pin "90") (pinfunction "IO_L05P_0/GCLK10_90") (pintype "bidirectional"))
    )
    (net (code "26") (name "/DDR_D7") (class "Default")
      (node (ref "U11") (pin "13") (pinfunction "DQ7_13") (pintype "bidirectional"))
      (node (ref "U4") (pin "91") (pinfunction "IO_L05N_0/GCLK11_91") (pintype "bidirectional"))
    )
    (net (code "27") (name "/DDR_D8") (class "Default")
      (node (ref "U11") (pin "42") (pinfunction "DQ8_42") (pintype "bidirectional"))
      (node (ref "U4") (pin "17") (pinfunction "IO_L06P_3/LHCLK6_17") (pintype "bidirectional"))
    )
    (net (code "28") (name "/DDR_D9") (class "Default")
      (node (ref "U11") (pin "44") (pinfunction "DQ9_44") (pintype "bidirectional"))
      (node (ref "U4") (pin "15") (pinfunction "IO_L05P_3/LHCLK4_15") (pintype "bidirectional"))
    )
    (net (code "29") (name "/DDR_D10") (class "Default")
      (node (ref "U11") (pin "45") (pinfunction "DQ10_45") (pintype "bidirectional"))
      (node (ref "U4") (pin "16") (pinfunction "IO_L05N_3/LHCLK5_16") (pintype "bidirectional"))
    )
    (net (code "30") (name "/DDR_D11") (class "Default")
      (node (ref "U11") (pin "47") (pinfunction "DQ11_47") (pintype "bidirectional"))
      (node (ref "U4") (pin "9") (pinfunction "IO_L03P_3/LHCLK0_9") (pintype "bidirectional"))
    )
    (net (code "31") (name "/DDR_D12") (class "Default")
      (node (ref "U11") (pin "48") (pinfunction "DQ12_48") (pintype "bidirectional"))
      (node (ref "U4") (pin "5") (pinfunction "IO_L02N_3/VREF_3_5") (pintype "bidirectional"))
    )
    (net (code "32") (name "/DDR_D13") (class "Default")
      (node (ref "U11") (pin "50") (pinfunction "DQ13_50") (pintype "bidirectional"))
      (node (ref "U4") (pin "4") (pinfunction "IO_L02P_3_4") (pintype "bidirectional"))
    )
    (net (code "33") (name "/DDR_D14") (class "Default")
      (node (ref "U11") (pin "51") (pinfunction "DQ14_51") (pintype "bidirectional"))
      (node (ref "U4") (pin "98") (pinfunction "IO_L07P_0_98") (pintype "bidirectional"))
    )
    (net (code "34") (name "/DDR_D15") (class "Default")
      (node (ref "U11") (pin "53") (pinfunction "DQ15_53") (pintype "bidirectional"))
      (node (ref "U4") (pin "99") (pinfunction "IO_L07N_0/HSWAP_99") (pintype "bidirectional"))
    )
    (net (code "35") (name "/DDR_~{CAS}") (class "Default")
      (node (ref "RA2") (pin "8") (pinfunction "8_8") (pintype "passive"))
      (node (ref "U11") (pin "17") (pinfunction "~{CAS}_17") (pintype "input"))
      (node (ref "U4") (pin "43") (pinfunction "IO_L07P_2/M0_43") (pintype "bidirectional"))
    )
    (net (code "36") (name "/DDR_~{WE}") (class "Default")
      (node (ref "U11") (pin "16") (pinfunction "~{WE}_16") (pintype "input"))
      (node (ref "U4") (pin "92") (pinfunction "IO_92") (pintype "bidirectional"))
    )
    (net (code "37") (name "/DONE") (class "Default")
      (node (ref "Q1") (pin "1") (pinfunction "B_1") (pintype "passive"))
      (node (ref "R24") (pin "1") (pintype "passive"))
      (node (ref "R26") (pin "1") (pintype "passive"))
      (node (ref "U4") (pin "51") (pinfunction "DONE_51") (pintype "bidirectional"))
      (node (ref "U9") (pin "1") (pinfunction "CE#_1") (pintype "input"))
    )
    (net (code "55") (name "/EXT_CLK") (class "Default")
      (node (ref "P1") (pin "19") (pinfunction "19_19") (pintype "passive"))
      (node (ref "U4") (pin "38") (pinfunction "IP_L05P_2/RDWR_B/GCLK0_38") (pintype "input"))
    )
    (net (code "56") (name "/FPGA_CLK") (class "Default")
      (node (ref "U4") (pin "89") (pinfunction "IP_L04N_0/GCLK9_89") (pintype "input"))
      (node (ref "X1") (pin "3") (pinfunction "OUT_3") (pintype "passive"))
    )
    (net (code "57") (name "/FPGA_TCK") (class "Default")
      (node (ref "RA1") (pin "2") (pinfunction "2_2") (pintype "passive"))
      (node (ref "U4") (pin "77") (pinfunction "TCK_77") (pintype "input"))
    )
    (net (code "58") (name "/FPGA_TDI") (class "Default")
      (node (ref "RA1") (pin "4") (pinfunction "4_4") (pintype "passive"))
      (node (ref "U4") (pin "100") (pinfunction "TDI_100") (pintype "input"))
    )
    (net (code "59") (name "/FPGA_TDO") (class "Default")
      (node (ref "RA1") (pin "3") (pinfunction "3_3") (pintype "passive"))
      (node (ref "U4") (pin "76") (pinfunction "TDO_76") (pintype "output"))
    )
    (net (code "60") (name "/FPGA_TMS") (class "Default")
      (node (ref "RA1") (pin "1") (pinfunction "1_1") (pintype "passive"))
      (node (ref "U4") (pin "75") (pinfunction "TMS_75") (pintype "input"))
    )
    (net (code "61") (name "/IO_1") (class "Default")
      (node (ref "P1") (pin "4") (pinfunction "4_4") (pintype "passive"))
      (node (ref "U4") (pin "94") (pinfunction "IO_L06P_0_94") (pintype "bidirectional"))
    )
    (net (code "62") (name "/IO_2") (class "Default")
      (node (ref "P1") (pin "5") (pinfunction "5_5") (pintype "passive"))
      (node (ref "U4") (pin "95") (pinfunction "IO_L06N_0/VREF_0_95") (pintype "bidirectional"))
    )
    (net (code "63") (name "/IO_3") (class "Default")
      (node (ref "P1") (pin "6") (pinfunction "6_6") (pintype "passive"))
      (node (ref "U4") (pin "2") (pinfunction "IO_L01P_3_2") (pintype "bidirectional"))
    )
    (net (code "64") (name "/IO_4") (class "Default")
      (node (ref "P1") (pin "7") (pinfunction "7_7") (pintype "passive"))
      (node (ref "U4") (pin "3") (pinfunction "IO_L01N_3_3") (pintype "bidirectional"))
    )
    (net (code "65") (name "/IO_5") (class "Default")
      (node (ref "P1") (pin "8") (pinfunction "8_8") (pintype "passive"))
      (node (ref "U4") (pin "11") (pinfunction "IO_L04P_3/LHCLK2_11") (pintype "bidirectional"))
    )
    (net (code "66") (name "/IO_6") (class "Default")
      (node (ref "J1") (pin "12") (pinfunction "12_12") (pintype "passive"))
      (node (ref "P1") (pin "9") (pinfunction "9_9") (pintype "passive"))
      (node (ref "U4") (pin "12") (pinfunction "IO_L04N_3/LHCLK3_12") (pintype "bidirectional"))
    )
    (net (code "67") (name "/IO_7") (class "Default")
      (node (ref "P1") (pin "10") (pinfunction "10_10") (pintype "passive"))
      (node (ref "U4") (pin "13") (pinfunction "IP_13") (pintype "input"))
    )
    (net (code "68") (name "/IO_8") (class "Default")
      (node (ref "J1") (pin "8") (pinfunction "8_8") (pintype "passive"))
      (node (ref "P1") (pin "11") (pinfunction "11_11") (pintype "passive"))
      (node (ref "U4") (pin "22") (pinfunction "IO_L07P_3_22") (pintype "bidirectional"))
    )
    (net (code "69") (name "/IO_9") (class "Default")
      (node (ref "J1") (pin "17") (pinfunction "17_17") (pintype "passive"))
      (node (ref "P1") (pin "12") (pinfunction "12_12") (pintype "passive"))
      (node (ref "U4") (pin "23") (pinfunction "IO_L07N_3_23") (pintype "bidirectional"))
    )
    (net (code "70") (name "/IO_10") (class "Default")
      (node (ref "P1") (pin "13") (pinfunction "13_13") (pintype "passive"))
      (node (ref "U4") (pin "30") (pinfunction "IP/VREF_2_30") (pintype "input"))
    )
    (net (code "71") (name "/IO_11") (class "Default")
      (node (ref "J1") (pin "15") (pinfunction "15_15") (pintype "passive"))
      (node (ref "P1") (pin "14") (pinfunction "14_14") (pintype "passive"))
      (node (ref "U4") (pin "32") (pinfunction "IO_L03P_2/D7/GCLK12_32") (pintype "bidirectional"))
    )
    (net (code "72") (name "/IO_12") (class "Default")
      (node (ref "J1") (pin "5") (pinfunction "5_5") (pintype "passive"))
      (node (ref "P1") (pin "15") (pinfunction "15_15") (pintype "passive"))
      (node (ref "U4") (pin "33") (pinfunction "IO_L03N_2/D6/GCLK13_33") (pintype "bidirectional"))
    )
    (net (code "73") (name "/IO_13") (class "Default")
      (node (ref "J1") (pin "7") (pinfunction "7_7") (pintype "passive"))
      (node (ref "P1") (pin "16") (pinfunction "16_16") (pintype "passive"))
      (node (ref "U4") (pin "34") (pinfunction "IO/D5_34") (pintype "bidirectional"))
    )
    (net (code "74") (name "/IO_14") (class "Default")
      (node (ref "J1") (pin "11") (pinfunction "11_11") (pintype "passive"))
      (node (ref "P1") (pin "17") (pinfunction "17_17") (pintype "passive"))
      (node (ref "U4") (pin "35") (pinfunction "IO_L04P_2/D4/GCLK14_35") (pintype "bidirectional"))
    )
    (net (code "75") (name "/IO_15") (class "Default")
      (node (ref "J1") (pin "13") (pinfunction "13_13") (pintype "passive"))
      (node (ref "P1") (pin "18") (pinfunction "18_18") (pintype "passive"))
      (node (ref "U4") (pin "36") (pinfunction "IO_L04N_2/D3/GCLK15_36") (pintype "bidirectional"))
    )
    (net (code "76") (name "/IO_16") (class "Default")
      (node (ref "J1") (pin "32") (pinfunction "32_32") (pintype "passive"))
      (node (ref "J1") (pin "37") (pinfunction "37_37") (pintype "passive"))
      (node (ref "P2") (pin "18") (pinfunction "18_18") (pintype "passive"))
      (node (ref "RA3") (pin "5") (pinfunction "5_5") (pintype "passive"))
      (node (ref "U4") (pin "47") (pinfunction "IO_L08P_2/VS2_47") (pintype "bidirectional"))
    )
    (net (code "77") (name "/IO_17") (class "Default")
      (node (ref "J1") (pin "33") (pinfunction "33_33") (pintype "passive"))
      (node (ref "J1") (pin "38") (pinfunction "38_38") (pintype "passive"))
      (node (ref "P2") (pin "17") (pinfunction "17_17") (pintype "passive"))
      (node (ref "RA3") (pin "7") (pinfunction "7_7") (pintype "passive"))
      (node (ref "U4") (pin "48") (pinfunction "IO_L08N_2/VS1_48") (pintype "bidirectional"))
    )
    (net (code "78") (name "/IO_18") (class "Default")
      (node (ref "J1") (pin "29") (pinfunction "29_29") (pintype "passive"))
      (node (ref "P2") (pin "19") (pinfunction "19_19") (pintype "passive"))
      (node (ref "R3") (pin "1") (pintype "passive"))
      (node (ref "RA2") (pin "7") (pinfunction "7_7") (pintype "passive"))
      (node (ref "U4") (pin "39") (pinfunction "IP_L05N_2/M2/GCLK1_39") (pintype "input"))
    )
    (net (code "79") (name "/IO_20") (class "Default")
      (node (ref "J1") (pin "14") (pinfunction "14_14") (pintype "passive"))
      (node (ref "P2") (pin "16") (pinfunction "16_16") (pintype "passive"))
      (node (ref "U4") (pin "53") (pinfunction "IO_L01P_1_53") (pintype "bidirectional"))
    )
    (net (code "80") (name "/IO_21") (class "Default")
      (node (ref "J1") (pin "19") (pinfunction "19_19") (pintype "passive"))
      (node (ref "P2") (pin "15") (pinfunction "15_15") (pintype "passive"))
      (node (ref "U4") (pin "54") (pinfunction "IO_L01N_1_54") (pintype "bidirectional"))
    )
    (net (code "81") (name "/IO_22") (class "Default")
      (node (ref "J1") (pin "27") (pinfunction "27_27") (pintype "passive"))
      (node (ref "J1") (pin "28") (pinfunction "28_28") (pintype "passive"))
      (node (ref "P2") (pin "14") (pinfunction "14_14") (pintype "passive"))
      (node (ref "U4") (pin "57") (pinfunction "IO_L02P_1_57") (pintype "bidirectional"))
    )
    (net (code "82") (name "/IO_23") (class "Default")
      (node (ref "J1") (pin "16") (pinfunction "16_16") (pintype "passive"))
      (node (ref "P2") (pin "13") (pinfunction "13_13") (pintype "passive"))
      (node (ref "U4") (pin "58") (pinfunction "IO_L02N_1_58") (pintype "bidirectional"))
    )
    (net (code "83") (name "/IO_24") (class "Default")
      (node (ref "J1") (pin "18") (pinfunction "18_18") (pintype "passive"))
      (node (ref "P2") (pin "12") (pinfunction "12_12") (pintype "passive"))
      (node (ref "U4") (pin "60") (pinfunction "IO_L03P_1/RHCLK0_60") (pintype "bidirectional"))
    )
    (net (code "84") (name "/IO_26") (class "Default")
      (node (ref "J1") (pin "6") (pinfunction "6_6") (pintype "passive"))
      (node (ref "P2") (pin "10") (pinfunction "10_10") (pintype "passive"))
      (node (ref "U4") (pin "67") (pinfunction "IO_L06P_1/RHCLK6_67") (pintype "bidirectional"))
    )
    (net (code "85") (name "/IO_27") (class "Default")
      (node (ref "P2") (pin "9") (pinfunction "9_9") (pintype "passive"))
      (node (ref "U4") (pin "68") (pinfunction "IO_L06N_1/RHCLK7_68") (pintype "bidirectional"))
    )
    (net (code "86") (name "/IO_28") (class "Default")
      (node (ref "P2") (pin "8") (pinfunction "8_8") (pintype "passive"))
      (node (ref "U4") (pin "69") (pinfunction "IP/VREF_1_69") (pintype "input"))
    )
    (net (code "87") (name "/IO_29") (class "Default")
      (node (ref "P2") (pin "7") (pinfunction "7_7") (pintype "passive"))
      (node (ref "U4") (pin "78") (pinfunction "IO_L01P_0_78") (pintype "bidirectional"))
    )
    (net (code "88") (name "/IO_30") (class "Default")
      (node (ref "P2") (pin "6") (pinfunction "6_6") (pintype "passive"))
      (node (ref "U4") (pin "79") (pinfunction "IO_L01N_0_79") (pintype "bidirectional"))
    )
    (net (code "89") (name "/IO_31") (class "Default")
      (node (ref "P2") (pin "5") (pinfunction "5_5") (pintype "passive"))
      (node (ref "U4") (pin "88") (pinfunction "IP_L04P_0/GCLK8_88") (pintype "input"))
    )
    (net (code "93") (name "/PROG_B") (class "Default")
      (node (ref "R23") (pin "1") (pintype "passive"))
      (node (ref "U4") (pin "1") (pinfunction "PROG_B_1") (pintype "input"))
    )
    (net (code "94") (name "/SHDN") (class "Default")
      (node (ref "P2") (pin "3") (pinfunction "3_3") (pintype "passive"))
      (node (ref "R18") (pin "1") (pintype "passive"))
      (node (ref "R25") (pin "1") (pintype "passive"))
      (node (ref "U1") (pin "5") (pinfunction "EN_5") (pintype "input"))
      (node (ref "U2") (pin "5") (pinfunction "EN_5") (pintype "input"))
      (node (ref "U3") (pin "5") (pinfunction "EN_5") (pintype "input"))
      (node (ref "U7") (pin "8") (pinfunction "~{SHDN2}_8") (pintype "input"))
      (node (ref "U7") (pin "9") (pinfunction "~{SHDN1}_9") (pintype "input"))
    )
    (net (code "95") (name "/SPI_CLK") (class "Default")
      (node (ref "U11") (pin "20") (pinfunction "BA0_20") (pintype "input"))
      (node (ref "U4") (pin "50") (pinfunction "IO_L09N_2/CCLK_50") (pintype "bidirectional"))
      (node (ref "U9") (pin "6") (pinfunction "SCK_6") (pintype "input"))
    )
    (net (code "96") (name "/SPI_MISO") (class "Default")
      (node (ref "U11") (pin "18") (pinfunction "~{RAS}_18") (pintype "input"))
      (node (ref "U4") (pin "44") (pinfunction "IO_L07N_2/DIN/D0_44") (pintype "bidirectional"))
      (node (ref "U9") (pin "2") (pinfunction "SO¦RY/BY#_2") (pintype "tri_state"))
    )
    (net (code "97") (name "/SPI_MOSI") (class "Default")
      (node (ref "U11") (pin "32") (pinfunction "A7_32") (pintype "input"))
      (node (ref "U4") (pin "27") (pinfunction "IO_L02N_2/MOSI/CSI_B_27") (pintype "bidirectional"))
      (node (ref "U9") (pin "5") (pinfunction "SI_5") (pintype "input"))
    )
    (net (code "98") (name "/SW1") (class "Default")
      (node (ref "L4") (pin "2") (pinfunction "2_2") (pintype "passive"))
      (node (ref "U7") (pin "2") (pinfunction "SW1_2") (pintype "passive"))
    )
    (net (code "99") (name "/SW2") (class "Default")
      (node (ref "C17") (pin "2") (pintype "passive"))
      (node (ref "L5") (pin "2") (pinfunction "2_2") (pintype "passive"))
      (node (ref "U7") (pin "4") (pinfunction "SW2_4") (pintype "passive"))
    )
    (net (code "100") (name "/VCOM") (class "Default")
      (node (ref "J1") (pin "22") (pinfunction "22_22") (pintype "passive"))
      (node (ref "U5") (pin "1") (pinfunction "OUT_1") (pintype "output"))
      (node (ref "U5") (pin "4") (pinfunction "IN-_4") (pintype "input"))
    )
    (net (code "104") (name "1.2V") (class "Default")
      (node (ref "C12") (pin "1") (pintype "passive"))
      (node (ref "C13") (pin "2") (pintype "passive"))
      (node (ref "C15") (pin "2") (pintype "passive"))
      (node (ref "C39") (pin "2") (pintype "passive"))
      (node (ref "C40") (pin "2") (pintype "passive"))
      (node (ref "C41") (pin "2") (pintype "passive"))
      (node (ref "C42") (pin "2") (pintype "passive"))
      (node (ref "L3") (pin "2") (pinfunction "2_2") (pintype "passive"))
      (node (ref "P1") (pin "3") (pinfunction "3_3") (pintype "passive"))
      (node (ref "R7") (pin "2") (pintype "passive"))
      (node (ref "U4") (pin "28") (pinfunction "VCCINT_28") (pintype "power_in"))
      (node (ref "U4") (pin "56") (pinfunction "VCCINT_56") (pintype "power_in"))
      (node (ref "U4") (pin "6") (pinfunction "VCCINT_6") (pintype "power_in"))
      (node (ref "U4") (pin "80") (pinfunction "VCCINT_80") (pintype "power_in"))
    )
    (net (code "105") (name "2.5V") (class "Default")
      (node (ref "C10") (pin "2") (pintype "passive"))
      (node (ref "C35") (pin "2") (pintype "passive"))
      (node (ref "C36") (pin "2") (pintype "passive"))
      (node (ref "C37") (pin "2") (pintype "passive"))
      (node (ref "C38") (pin "2") (pintype "passive"))
      (node (ref "C7") (pin "1") (pintype "passive"))
      (node (ref "C8") (pin "2") (pintype "passive"))
      (node (ref "L2") (pin "2") (pinfunction "2_2") (pintype "passive"))
      (node (ref "P1") (pin "2") (pinfunction "2_2") (pintype "passive"))
      (node (ref "P3") (pin "5") (pinfunction "5_5") (pintype "passive"))
      (node (ref "R23") (pin "2") (pintype "passive"))
      (node (ref "R24") (pin "2") (pintype "passive"))
      (node (ref "R4") (pin "2") (pintype "passive"))
      (node (ref "U4") (pin "21") (pinfunction "VCCAUX_21") (pintype "power_in"))
      (node (ref "U4") (pin "46") (pinfunction "VCCAUX_46") (pintype "power_in"))
      (node (ref "U4") (pin "74") (pinfunction "VCCAUX_74") (pintype "power_in"))
      (node (ref "U4") (pin "96") (pinfunction "VCCAUX_96") (pintype "power_in"))
    )
    (net (code "106") (name "3.3V") (class "Default")
      (node (ref "C14") (pin "2") (pintype "passive"))
      (node (ref "C26") (pin "2") (pintype "passive"))
      (node (ref "C27") (pin "2") (pintype "passive"))
      (node (ref "C28") (pin "2") (pintype "passive"))
      (node (ref "C29") (pin "2") (pintype "passive"))
      (node (ref "C3") (pin "2") (pintype "passive"))
      (node (ref "C30") (pin "2") (pintype "passive"))
      (node (ref "C31") (pin "2") (pintype "passive"))
      (node (ref "C33") (pin "2") (pintype "passive"))
      (node (ref "C34") (pin "2") (pintype "passive"))
      (node (ref "C4") (pin "1") (pintype "passive"))
      (node (ref "C43") (pin "2") (pintype "passive"))
      (node (ref "C44") (pin "2") (pintype "passive"))
      (node (ref "C45") (pin "2") (pintype "passive"))
      (node (ref "C46") (pin "2") (pintype "passive"))
      (node (ref "C47") (pin "2") (pintype "passive"))
      (node (ref "C48") (pin "2") (pintype "passive"))
      (node (ref "C49") (pin "2") (pintype "passive"))
      (node (ref "C5") (pin "2") (pintype "passive"))
      (node (ref "C50") (pin "2") (pintype "passive"))
      (node (ref "J1") (pin "30") (pinfunction "30_30") (pintype "passive"))
      (node (ref "J1") (pin "35") (pinfunction "35_35") (pintype "passive"))
      (node (ref "J1") (pin "36") (pinfunction "36_36") (pintype "passive"))
      (node (ref "J1") (pin "4") (pinfunction "4_4") (pintype "passive"))
      (node (ref "L1") (pin "2") (pinfunction "2_2") (pintype "passive"))
      (node (ref "L4") (pin "1") (pinfunction "1_1") (pintype "passive"))
      (node (ref "L5") (pin "1") (pinfunction "1_1") (pintype "passive"))
      (node (ref "P2") (pin "2") (pinfunction "2_2") (pintype "passive"))
      (node (ref "R1") (pin "2") (pintype "passive"))
      (node (ref "R22") (pin "2") (pintype "passive"))
      (node (ref "R25") (pin "2") (pintype "passive"))
      (node (ref "RA2") (pin "1") (pinfunction "1_1") (pintype "passive"))
      (node (ref "RA3") (pin "1") (pinfunction "1_1") (pintype "passive"))
      (node (ref "RA3") (pin "2") (pinfunction "2_2") (pintype "passive"))
      (node (ref "RA3") (pin "3") (pinfunction "3_3") (pintype "passive"))
      (node (ref "RA3") (pin "4") (pinfunction "4_4") (pintype "passive"))
      (node (ref "U11") (pin "1") (pinfunction "VDD_1") (pintype "power_in"))
      (node (ref "U11") (pin "14") (pinfunction "VDD_14") (pintype "power_in"))
      (node (ref "U11") (pin "27") (pinfunction "VDD_27") (pintype "power_in"))
      (node (ref "U11") (pin "3") (pinfunction "VDDQ_3") (pintype "power_in"))
      (node (ref "U11") (pin "37") (pinfunction "CKE_37") (pintype "input"))
      (node (ref "U11") (pin "43") (pinfunction "VDDQ_43") (pintype "power_in"))
      (node (ref "U11") (pin "49") (pinfunction "VDDQ_49") (pintype "power_in"))
      (node (ref "U11") (pin "9") (pinfunction "VDDQ_9") (pintype "power_in"))
      (node (ref "U4") (pin "20") (pinfunction "VCCO_3_20") (pintype "power_in"))
      (node (ref "U4") (pin "31") (pinfunction "VCCO_2_31") (pintype "power_in"))
      (node (ref "U4") (pin "45") (pinfunction "VCCO_2_45") (pintype "power_in"))
      (node (ref "U4") (pin "55") (pinfunction "VCCO_1_55") (pintype "power_in"))
      (node (ref "U4") (pin "73") (pinfunction "VCCO_1_73") (pintype "power_in"))
      (node (ref "U4") (pin "8") (pinfunction "VCCO_3_8") (pintype "power_in"))
      (node (ref "U4") (pin "82") (pinfunction "VCCO_0_82") (pintype "power_in"))
      (node (ref "U4") (pin "97") (pinfunction "VCCO_0_97") (pintype "power_in"))
      (node (ref "U7") (pin "3") (pinfunction "VIN_3") (pintype "power_in"))
      (node (ref "U9") (pin "3") (pinfunction "WP#_3") (pintype "input"))
      (node (ref "U9") (pin "7") (pinfunction "HOLD#_7") (pintype "input"))
      (node (ref "U9") (pin "8") (pinfunction "VDD_8") (pintype "power_in"))
      (node (ref "X1") (pin "1") (pinfunction "OE_1") (pintype "passive"))
      (node (ref "X1") (pin "4") (pinfunction "VCC_4") (pintype "passive"))
    )
    (net (code "107") (name "GND") (class "Default")
      (node (ref "C1") (pin "1") (pintype "passive"))
      (node (ref "C11") (pin "1") (pintype "passive"))
      (node (ref "C12") (pin "2") (pintype "passive"))
      (node (ref "C13") (pin "1") (pintype "passive"))
      (node (ref "C14") (pin "1") (pintype "passive"))
      (node (ref "C16") (pin "1") (pintype "passive"))
      (node (ref "C18") (pin "1") (pintype "passive"))
      (node (ref "C2") (pin "2") (pintype "passive"))
      (node (ref "C20") (pin "2") (pintype "passive"))
      (node (ref "C21") (pin "1") (pintype "passive"))
      (node (ref "C22") (pin "1") (pintype "passive"))
      (node (ref "C23") (pin "1") (pintype "passive"))
      (node (ref "C24") (pin "1") (pintype "passive"))
      (node (ref "C25") (pin "1") (pintype "passive"))
      (node (ref "C26") (pin "1") (pintype "passive"))
      (node (ref "C27") (pin "1") (pintype "passive"))
      (node (ref "C28") (pin "1") (pintype "passive"))
      (node (ref "C29") (pin "1") (pintype "passive"))
      (node (ref "C3") (pin "1") (pintype "passive"))
      (node (ref "C30") (pin "1") (pintype "passive"))
      (node (ref "C31") (pin "1") (pintype "passive"))
      (node (ref "C33") (pin "1") (pintype "passive"))
      (node (ref "C34") (pin "1") (pintype "passive"))
      (node (ref "C35") (pin "1") (pintype "passive"))
      (node (ref "C36") (pin "1") (pintype "passive"))
      (node (ref "C37") (pin "1") (pintype "passive"))
      (node (ref "C38") (pin "1") (pintype "passive"))
      (node (ref "C39") (pin "1") (pintype "passive"))
      (node (ref "C4") (pin "2") (pintype "passive"))
      (node (ref "C40") (pin "1") (pintype "passive"))
      (node (ref "C41") (pin "1") (pintype "passive"))
      (node (ref "C42") (pin "1") (pintype "passive"))
      (node (ref "C43") (pin "1") (pintype "passive"))
      (node (ref "C44") (pin "1") (pintype "passive"))
      (node (ref "C45") (pin "1") (pintype "passive"))
      (node (ref "C46") (pin "1") (pintype "passive"))
      (node (ref "C47") (pin "1") (pintype "passive"))
      (node (ref "C48") (pin "1") (pintype "passive"))
      (node (ref "C49") (pin "1") (pintype "passive"))
      (node (ref "C50") (pin "1") (pintype "passive"))
      (node (ref "C6") (pin "1") (pintype "passive"))
      (node (ref "C7") (pin "2") (pintype "passive"))
      (node (ref "C8") (pin "1") (pintype "passive"))
      (node (ref "J1") (pin "3") (pinfunction "3_3") (pintype "passive"))
      (node (ref "J1") (pin "31") (pinfunction "31_31") (pintype "passive"))
      (node (ref "J1") (pin "34") (pinfunction "34_34") (pintype "passive"))
      (node (ref "P1") (pin "1") (pinfunction "1_1") (pintype "passive"))
      (node (ref "P2") (pin "4") (pinfunction "4_4") (pintype "passive"))
      (node (ref "P3") (pin "6") (pinfunction "6_6") (pintype "passive"))
      (node (ref "P5") (pin "1") (pinfunction "1_1") (pintype "passive"))
      (node (ref "P6") (pin "1") (pinfunction "1_1") (pintype "passive"))
      (node (ref "Q1") (pin "2") (pinfunction "E_2") (pintype "passive"))
      (node (ref "R10") (pin "2") (pintype "passive"))
      (node (ref "R12") (pin "1") (pintype "passive"))
      (node (ref "R14") (pin "1") (pintype "passive"))
      (node (ref "R17") (pin "2") (pintype "passive"))
      (node (ref "R26") (pin "2") (pintype "passive"))
      (node (ref "R3") (pin "2") (pintype "passive"))
      (node (ref "R5") (pin "1") (pintype "passive"))
      (node (ref "R8") (pin "1") (pintype "passive"))
      (node (ref "RA2") (pin "2") (pinfunction "2_2") (pintype "passive"))
      (node (ref "RA2") (pin "3") (pinfunction "3_3") (pintype "passive"))
      (node (ref "RA2") (pin "4") (pinfunction "4_4") (pintype "passive"))
      (node (ref "U1") (pin "1") (pinfunction "PGND_1") (pintype "power_in"))
      (node (ref "U1") (pin "3") (pinfunction "AGND_3") (pintype "power_in"))
      (node (ref "U1") (pin "9") (pinfunction "PP_9") (pintype "power_in"))
      (node (ref "U11") (pin "12") (pinfunction "VSSQ_12") (pintype "power_in"))
      (node (ref "U11") (pin "15") (pinfunction "LDQM_15") (pintype "input"))
      (node (ref "U11") (pin "19") (pinfunction "~{CS}_19") (pintype "input"))
      (node (ref "U11") (pin "28") (pinfunction "VSS_28") (pintype "power_in"))
      (node (ref "U11") (pin "39") (pinfunction "UDQM_39") (pintype "input"))
      (node (ref "U11") (pin "41") (pinfunction "VSS_41") (pintype "power_in"))
      (node (ref "U11") (pin "46") (pinfunction "VSSQ_46") (pintype "power_in"))
      (node (ref "U11") (pin "52") (pinfunction "VSSQ_52") (pintype "power_in"))
      (node (ref "U11") (pin "54") (pinfunction "VSS_54") (pintype "power_in"))
      (node (ref "U11") (pin "6") (pinfunction "VSSQ_6") (pintype "power_in"))
      (node (ref "U2") (pin "1") (pinfunction "PGND_1") (pintype "power_in"))
      (node (ref "U2") (pin "3") (pinfunction "AGND_3") (pintype "power_in"))
      (node (ref "U2") (pin "9") (pinfunction "PP_9") (pintype "power_in"))
      (node (ref "U3") (pin "1") (pinfunction "PGND_1") (pintype "power_in"))
      (node (ref "U3") (pin "3") (pinfunction "AGND_3") (pintype "power_in"))
      (node (ref "U3") (pin "9") (pinfunction "PP_9") (pintype "power_in"))
      (node (ref "U4") (pin "14") (pinfunction "GND_14") (pintype "power_in"))
      (node (ref "U4") (pin "19") (pinfunction "GND_19") (pintype "power_in"))
      (node (ref "U4") (pin "29") (pinfunction "GND_29") (pintype "power_in"))
      (node (ref "U4") (pin "37") (pinfunction "GND_37") (pintype "power_in"))
      (node (ref "U4") (pin "52") (pinfunction "GND_52") (pintype "power_in"))
      (node (ref "U4") (pin "59") (pinfunction "GND_59") (pintype "power_in"))
      (node (ref "U4") (pin "64") (pinfunction "GND_64") (pintype "power_in"))
      (node (ref "U4") (pin "7") (pinfunction "GND_7") (pintype "power_in"))
      (node (ref "U4") (pin "72") (pinfunction "GND_72") (pintype "power_in"))
      (node (ref "U4") (pin "81") (pinfunction "GND_81") (pintype "power_in"))
      (node (ref "U4") (pin "87") (pinfunction "GND_87") (pintype "power_in"))
      (node (ref "U4") (pin "93") (pinfunction "GND_93") (pintype "power_in"))
      (node (ref "U6") (pin "4") (pinfunction "GND_4") (pintype "power_in"))
      (node (ref "U6") (pin "9") (pinfunction "EP_9") (pintype "power_in"))
      (node (ref "U7") (pin "11") (pinfunction "EP_11") (pintype "power_in"))
      (node (ref "U8") (pin "4") (pinfunction "GND_4") (pintype "power_in"))
      (node (ref "U8") (pin "9") (pinfunction "EP_9") (pintype "passive"))
      (node (ref "U9") (pin "4") (pinfunction "VSS_4") (pintype "power_in"))
      (node (ref "X1") (pin "2") (pinfunction "GND_2") (pintype "passive"))
    )
    (net (code "108") (name "Net-(LED1-PadA)") (class "Default")
      (node (ref "LED1") (pin "A") (pinfunction "A_A") (pintype "passive"))
      (node (ref "R22") (pin "1") (pintype "passive"))
    )
    (net (code "109") (name "Net-(P3-Pad1)") (class "Default")
      (node (ref "P3") (pin "1") (pinfunction "1_1") (pintype "passive"))
      (node (ref "RA1") (pin "5") (pinfunction "5_5") (pintype "passive"))
    )
    (net (code "110") (name "Net-(P3-Pad2)") (class "Default")
      (node (ref "P3") (pin "2") (pinfunction "2_2") (pintype "passive"))
      (node (ref "RA1") (pin "6") (pinfunction "6_6") (pintype "passive"))
    )
    (net (code "111") (name "Net-(P3-Pad3)") (class "Default")
      (node (ref "P3") (pin "3") (pinfunction "3_3") (pintype "passive"))
      (node (ref "RA1") (pin "7") (pinfunction "7_7") (pintype "passive"))
    )
    (net (code "112") (name "Net-(P3-Pad4)") (class "Default")
      (node (ref "P3") (pin "4") (pinfunction "4_4") (pintype "passive"))
      (node (ref "RA1") (pin "8") (pinfunction "8_8") (pintype "passive"))
    )
    (net (code "113") (name "Net-(Q1-C)") (class "Default")
      (node (ref "LED1") (pin "K") (pinfunction "K_K") (pintype "passive"))
      (node (ref "Q1") (pin "3") (pinfunction "C_3") (pintype "passive"))
    )
    (net (code "114") (name "Net-(U1-FB)") (class "Default")
      (node (ref "C5") (pin "1") (pintype "passive"))
      (node (ref "R1") (pin "1") (pintype "passive"))
      (node (ref "R14") (pin "2") (pintype "passive"))
      (node (ref "U1") (pin "4") (pinfunction "FB_4") (pintype "input"))
    )
    (net (code "115") (name "Net-(U1-SW)") (class "Default")
      (node (ref "L1") (pin "1") (pinfunction "1_1") (pintype "passive"))
      (node (ref "U1") (pin "2") (pinfunction "SW_2") (pintype "power_in"))
    )
    (net (code "116") (name "Net-(U2-FB)") (class "Default")
      (node (ref "C10") (pin "1") (pintype "passive"))
      (node (ref "R4") (pin "1") (pintype "passive"))
      (node (ref "R5") (pin "2") (pintype "passive"))
      (node (ref "U2") (pin "4") (pinfunction "FB_4") (pintype "input"))
    )
    (net (code "117") (name "Net-(U2-SW)") (class "Default")
      (node (ref "L2") (pin "1") (pinfunction "1_1") (pintype "passive"))
      (node (ref "U2") (pin "2") (pinfunction "SW_2") (pintype "power_in"))
    )
    (net (code "118") (name "Net-(U3-FB)") (class "Default")
      (node (ref "C15") (pin "1") (pintype "passive"))
      (node (ref "R7") (pin "1") (pintype "passive"))
      (node (ref "R8") (pin "2") (pintype "passive"))
      (node (ref "U3") (pin "4") (pinfunction "FB_4") (pintype "input"))
    )
    (net (code "119") (name "Net-(U3-SW)") (class "Default")
      (node (ref "L3") (pin "1") (pinfunction "1_1") (pintype "passive"))
      (node (ref "U3") (pin "2") (pinfunction "SW_2") (pintype "power_in"))
    )
    (net (code "120") (name "Net-(U5-IN+)") (class "Default")
      (node (ref "R19") (pin "1") (pintype "passive"))
      (node (ref "R20") (pin "1") (pintype "passive"))
      (node (ref "R21") (pin "2") (pintype "passive"))
      (node (ref "U5") (pin "3") (pinfunction "IN+_3") (pintype "input"))
    )
    (net (code "121") (name "Net-(U6-FB)") (class "Default")
      (node (ref "C9") (pin "2") (pintype "passive"))
      (node (ref "R10") (pin "1") (pintype "passive"))
      (node (ref "R2") (pin "1") (pintype "passive"))
      (node (ref "U6") (pin "2") (pinfunction "FB_2") (pintype "input"))
    )
    (net (code "122") (name "Net-(U6-NR{slash}SS)") (class "Default")
      (node (ref "C16") (pin "2") (pintype "passive"))
      (node (ref "U6") (pin "6") (pinfunction "NR/SS_6") (pintype "passive"))
    )
    (net (code "123") (name "Net-(U7-D2)") (class "Default")
      (node (ref "C17") (pin "1") (pintype "passive"))
      (node (ref "D1") (pin "K") (pinfunction "K_K") (pintype "passive"))
      (node (ref "U7") (pin "5") (pinfunction "D2_5") (pintype "passive"))
    )
    (net (code "124") (name "Net-(U7-FB1)") (class "Default")
      (node (ref "R11") (pin "1") (pintype "passive"))
      (node (ref "R12") (pin "2") (pintype "passive"))
      (node (ref "U7") (pin "10") (pinfunction "FB1_10") (pintype "input"))
    )
    (net (code "125") (name "Net-(U7-FB2)") (class "Default")
      (node (ref "R13") (pin "1") (pintype "passive"))
      (node (ref "R15") (pin "2") (pintype "passive"))
      (node (ref "U7") (pin "6") (pinfunction "FB2_6") (pintype "input"))
    )
    (net (code "126") (name "Net-(U7-VREF)") (class "Default")
      (node (ref "R15") (pin "1") (pintype "passive"))
      (node (ref "U7") (pin "7") (pinfunction "VREF_7") (pintype "input"))
    )
    (net (code "127") (name "Net-(U8-FB)") (class "Default")
      (node (ref "C19") (pin "2") (pintype "passive"))
      (node (ref "R16") (pin "1") (pintype "passive"))
      (node (ref "R17") (pin "1") (pintype "passive"))
      (node (ref "U8") (pin "2") (pinfunction "FB_2") (pintype "input"))
    )
    (net (code "128") (name "Net-(U8-NR{slash}SS)") (class "Default")
      (node (ref "C20") (pin "1") (pintype "passive"))
      (node (ref "U8") (pin "6") (pinfunction "NR/SS_6") (pintype "passive"))
    )
    (net (code "129") (name "VIN") (class "Default")
      (node (ref "C1") (pin "2") (pintype "passive"))
      (node (ref "C11") (pin "2") (pintype "passive"))
      (node (ref "C2") (pin "1") (pintype "passive"))
      (node (ref "C6") (pin "2") (pintype "passive"))
      (node (ref "P2") (pin "1") (pinfunction "1_1") (pintype "passive"))
      (node (ref "P4") (pin "1") (pinfunction "1_1") (pintype "passive"))
      (node (ref "R18") (pin "2") (pintype "passive"))
      (node (ref "U1") (pin "6") (pinfunction "PG_6") (pintype "open_collector"))
      (node (ref "U1") (pin "7") (pinfunction "AVIN_7") (pintype "power_in"))
      (node (ref "U1") (pin "8") (pinfunction "PVIN_8") (pintype "power_in"))
      (node (ref "U2") (pin "6") (pinfunction "PG_6") (pintype "open_collector"))
      (node (ref "U2") (pin "7") (pinfunction "AVIN_7") (pintype "power_in"))
      (node (ref "U2") (pin "8") (pinfunction "PVIN_8") (pintype "power_in"))
      (node (ref "U3") (pin "6") (pinfunction "PG_6") (pintype "open_collector"))
      (node (ref "U3") (pin "7") (pinfunction "AVIN_7") (pintype "power_in"))
      (node (ref "U3") (pin "8") (pinfunction "PVIN_8") (pintype "power_in"))
    )
    (net (code "130") (name "unconnected-(J1-Pad9)") (class "Default")
      (node (ref "J1") (pin "9") (pinfunction "9_9") (pintype "passive"))
    )
    (net (code "131") (name "unconnected-(J1-Pad10)") (class "Default")
      (node (ref "J1") (pin "10") (pinfunction "10_10") (pintype "passive"))
    )
    (net (code "132") (name "unconnected-(J1-Pad20)") (class "Default")
      (node (ref "J1") (pin "20") (pinfunction "20_20") (pintype "passive"))
    )
    (net (code "133") (name "unconnected-(J1-Pad21)") (class "Default")
      (node (ref "J1") (pin "21") (pinfunction "21_21") (pintype "passive"))
    )
    (net (code "134") (name "unconnected-(J1-Pad26)") (class "Default")
      (node (ref "J1") (pin "26") (pinfunction "26_26") (pintype "passive"))
    )
    (net (code "135") (name "unconnected-(J1-Pad39)") (class "Default")
      (node (ref "J1") (pin "39") (pinfunction "39_39") (pintype "passive"))
    )
    (net (code "136") (name "unconnected-(J1-Pad40)") (class "Default")
      (node (ref "J1") (pin "40") (pinfunction "40_40") (pintype "passive"))
    )
    (net (code "137") (name "unconnected-(J1-Pad41)") (class "Default")
      (node (ref "J1") (pin "41") (pinfunction "41_41") (pintype "passive"))
    )
    (net (code "138") (name "unconnected-(RA2-Pad6)") (class "Default")
      (node (ref "RA2") (pin "6") (pinfunction "6_6") (pintype "passive"))
    )
    (net (code "139") (name "unconnected-(RA3-Pad8)") (class "Default")
      (node (ref "RA3") (pin "8") (pinfunction "8_8") (pintype "passive"))
    )
    (net (code "140") (name "unconnected-(U6-DNC-Pad7)") (class "Default")
      (node (ref "U6") (pin "7") (pinfunction "DNC_7") (pintype "passive"))
    )
    (net (code "141") (name "unconnected-(U6-NC-Pad3)") (class "Default")
      (node (ref "U6") (pin "3") (pinfunction "NC_3") (pintype "passive"))
    )
    (net (code "142") (name "unconnected-(U8-DNC-Pad7)") (class "Default")
      (node (ref "U8") (pin "7") (pinfunction "DNC_7") (pintype "passive"))
    )
    (net (code "143") (name "unconnected-(U8-NC-Pad3)") (class "Default")
      (node (ref "U8") (pin "3") (pinfunction "NC_3") (pintype "passive"))
    )
    (net (code "144") (name "unconnected-(U11-NC{slash}RFU-Pad40)") (class "Default")
      (node (ref "U11") (pin "40") (pinfunction "NC/RFU_40") (pintype "passive"))
    )
  )
)
